# Adapter-IO4-LED.net
KiCad netlist of a schematic drawn in EAGLE
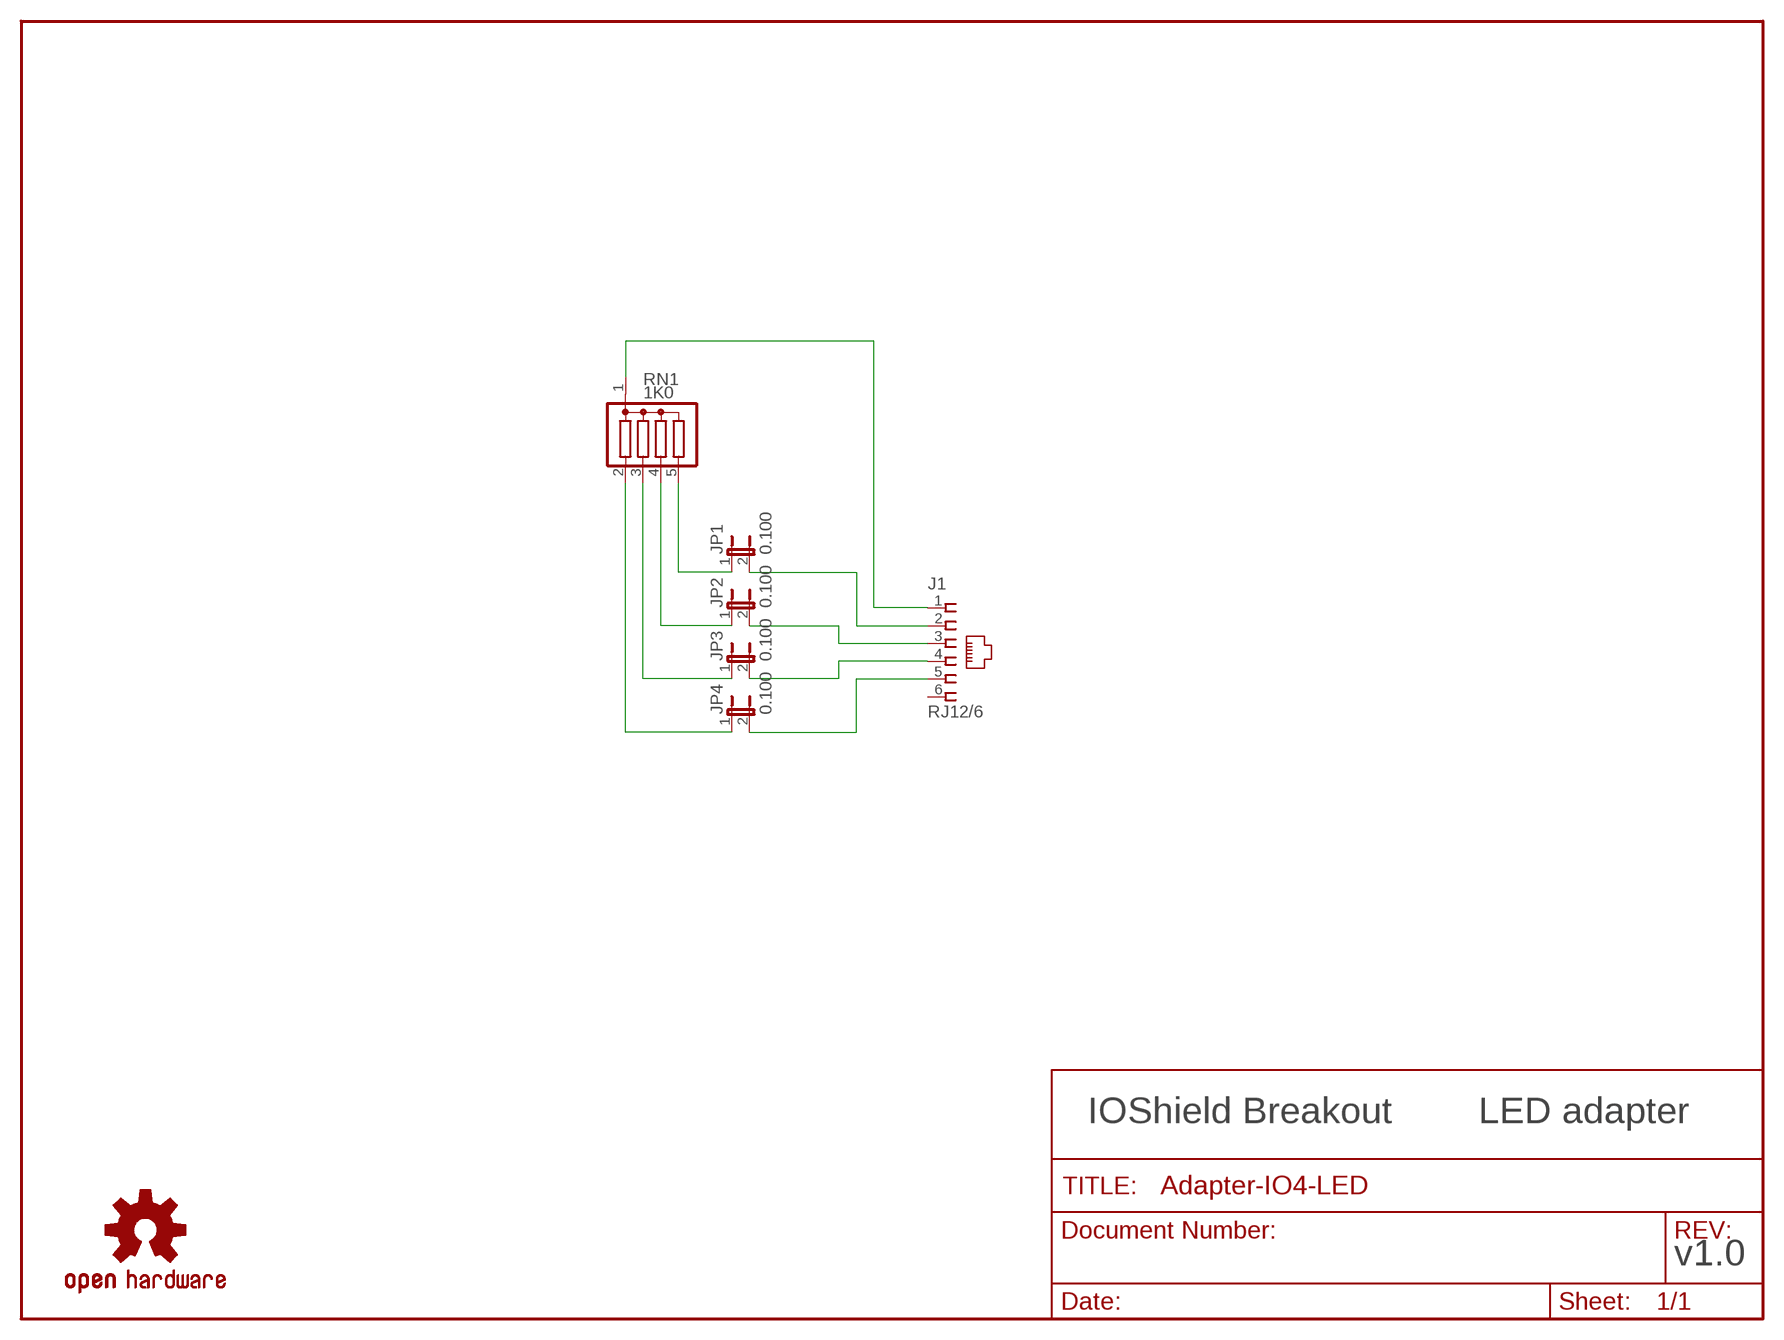
[diagram p0: schematic, sheet 1]

(export (version "E")
  (design (tool "Eeschema 10.0.6"))
  (components
    (comp (ref "J1")
      (value "RJ12/6")
      (footprint "eagle-import:RJ25-PANEL")
      (libsource (lib "eagle-import") (part "CONNECTOR-RJ25-6P6C"))
    )
    (comp (ref "JP1")
      (value "0.100")
      (footprint "eagle-import:1X02_LOCK")
      (libsource (lib "eagle-import") (part "JUMPER-2PTH_LOCK"))
    )
    (comp (ref "JP2")
      (value "0.100")
      (footprint "eagle-import:1X02_LOCK")
      (libsource (lib "eagle-import") (part "JUMPER-2PTH_LOCK"))
    )
    (comp (ref "JP3")
      (value "0.100")
      (footprint "eagle-import:1X02_LOCK")
      (libsource (lib "eagle-import") (part "JUMPER-2PTH_LOCK"))
    )
    (comp (ref "JP4")
      (value "0.100")
      (footprint "eagle-import:1X02_LOCK")
      (libsource (lib "eagle-import") (part "JUMPER-2PTH_LOCK"))
    )
    (comp (ref "RN1")
      (value "1K0")
      (footprint "eagle-import:SIL5")
      (libsource (lib "eagle-import") (part "G04R"))
    )
    (comp (ref "U$1")
      (value "OSHW")
      (footprint "eagle-import:OSHW-LOGO-M")
      (libsource (lib "eagle-import") (part "DOC-OSHW-LOGO-M"))
    )
  )
  (nets
    (net (code "1") (name "Net-(J1-Pad1)") (class "Default")
      (node (ref "J1") (pin "1") (pinfunction "1_1") (pintype "passive"))
      (node (ref "RN1") (pin "1") (pinfunction "1_1") (pintype "passive"))
    )
    (net (code "2") (name "Net-(J1-Pad2)") (class "Default")
      (node (ref "J1") (pin "2") (pinfunction "2_2") (pintype "passive"))
      (node (ref "JP1") (pin "2") (pinfunction "2_2") (pintype "passive"))
    )
    (net (code "3") (name "Net-(J1-Pad3)") (class "Default")
      (node (ref "J1") (pin "3") (pinfunction "3_3") (pintype "passive"))
      (node (ref "JP2") (pin "2") (pinfunction "2_2") (pintype "passive"))
    )
    (net (code "4") (name "Net-(J1-Pad4)") (class "Default")
      (node (ref "J1") (pin "4") (pinfunction "4_4") (pintype "passive"))
      (node (ref "JP3") (pin "2") (pinfunction "2_2") (pintype "passive"))
    )
    (net (code "5") (name "Net-(J1-Pad5)") (class "Default")
      (node (ref "J1") (pin "5") (pinfunction "5_5") (pintype "passive"))
      (node (ref "JP4") (pin "2") (pinfunction "2_2") (pintype "passive"))
    )
    (net (code "6") (name "Net-(JP1-Pad1)") (class "Default")
      (node (ref "JP1") (pin "1") (pinfunction "1_1") (pintype "passive"))
      (node (ref "RN1") (pin "5") (pinfunction "5_5") (pintype "passive"))
    )
    (net (code "7") (name "Net-(JP2-Pad1)") (class "Default")
      (node (ref "JP2") (pin "1") (pinfunction "1_1") (pintype "passive"))
      (node (ref "RN1") (pin "4") (pinfunction "4_4") (pintype "passive"))
    )
    (net (code "8") (name "Net-(JP3-Pad1)") (class "Default")
      (node (ref "JP3") (pin "1") (pinfunction "1_1") (pintype "passive"))
      (node (ref "RN1") (pin "3") (pinfunction "3_3") (pintype "passive"))
    )
    (net (code "9") (name "Net-(JP4-Pad1)") (class "Default")
      (node (ref "JP4") (pin "1") (pinfunction "1_1") (pintype "passive"))
      (node (ref "RN1") (pin "2") (pinfunction "2_2") (pintype "passive"))
    )
    (net (code "10") (name "unconnected-(J1-Pad6)") (class "Default")
      (node (ref "J1") (pin "6") (pinfunction "6_6") (pintype "passive"))
    )
  )
)
